# 2S1P_BatteryPack_V100.net
KiCad netlist of a schematic drawn in Altium Designer
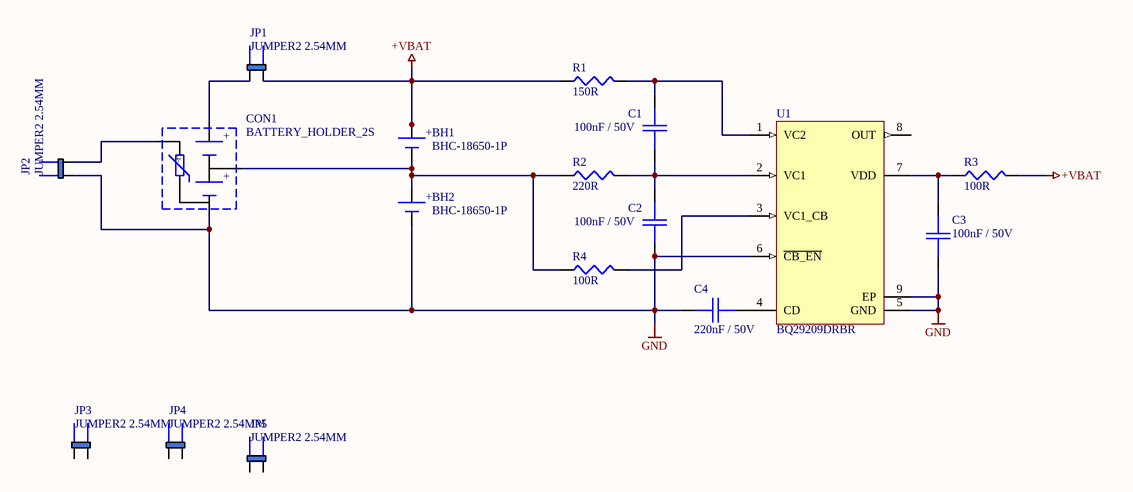
[diagram p0: 2S1P_BatteryPack_V100.SchDoc]

(export (version "E")
  (design (tool "Eeschema 10.0.6"))
  (components
    (comp (ref "BH1")
      (value "BHC-18650-1P")
      (footprint "18650_HOLDER")
      (description "18650 Battery Cell Holder THT")
      (libsource (lib "ALTIUM_DB_LIB") (part "BATTERY_HOLDER_18650"))
    )
    (comp (ref "BH2")
      (value "BHC-18650-1P")
      (footprint "18650_HOLDER")
      (description "18650 Battery Cell Holder THT")
      (libsource (lib "ALTIUM_DB_LIB") (part "BATTERY_HOLDER_18650"))
    )
    (comp (ref "C1")
      (value "100nF / 50V")
      (footprint "0805_C")
      (description "100nF 50V X7R")
      (fields (field (name "PART NUMBER") "SMD0805-100nF-50V"))
      (libsource (lib "ALTIUM_DB_LIB") (part "CAP_NONPOL"))
    )
    (comp (ref "C2")
      (value "100nF / 50V")
      (footprint "0805_C")
      (description "100nF 50V X7R")
      (fields (field (name "PART NUMBER") "SMD0805-100nF-50V"))
      (libsource (lib "ALTIUM_DB_LIB") (part "CAP_NONPOL"))
    )
    (comp (ref "C3")
      (value "100nF / 50V")
      (footprint "0805_C")
      (description "100nF 50V X7R")
      (fields (field (name "PART NUMBER") "SMD0805-100nF-50V"))
      (libsource (lib "ALTIUM_DB_LIB") (part "CAP_NONPOL"))
    )
    (comp (ref "C4")
      (value "220nF / 50V")
      (footprint "0805_C")
      (description "220nF 50V Y5V")
      (fields (field (name "PART NUMBER") "SMD0805-220nF-50V"))
      (libsource (lib "ALTIUM_DB_LIB") (part "CAP_NONPOL"))
    )
    (comp (ref "CON1")
      (value "BATTERY_HOLDER_2S")
      (footprint "MOLEX-53253-0470")
      (description "2S Battery with NTC thermistor")
      (libsource (lib "ALTIUM_DB_LIB") (part "BATTERY_HOLDER_2S"))
    )
    (comp (ref "JP1")
      (value "JUMPER2 2.54MM")
      (footprint "JUMPER_5")
      (libsource (lib "ALTIUM_DB_LIB") (part "JUMPER2"))
    )
    (comp (ref "JP2") (value "JUMPER2 2.54MM") (footprint "JUMPER_5") (libsource (lib "") (part "JUMPER2_1")))
    (comp (ref "JP3")
      (value "JUMPER2 2.54MM")
      (footprint "JUMPER_5")
      (libsource (lib "ALTIUM_DB_LIB") (part "JUMPER2"))
    )
    (comp (ref "JP4")
      (value "JUMPER2 2.54MM")
      (footprint "JUMPER_5")
      (libsource (lib "ALTIUM_DB_LIB") (part "JUMPER2"))
    )
    (comp (ref "JP5")
      (value "JUMPER2 2.54MM")
      (footprint "JUMPER_5")
      (libsource (lib "ALTIUM_DB_LIB") (part "JUMPER2"))
    )
    (comp (ref "R1")
      (value "150R")
      (footprint "0805")
      (description "150R 0805 0.125W 5%")
      (fields (field (name "PART NUMBER") "SMD0805-150R 5%"))
      (libsource (lib "ALTIUM_DB_LIB") (part "RESISTOR"))
    )
    (comp (ref "R2")
      (value "220R")
      (footprint "0805")
      (description "220R 0805 0.125W 5%")
      (fields (field (name "PART NUMBER") "SMD0805-220R 5%"))
      (libsource (lib "ALTIUM_DB_LIB") (part "RESISTOR"))
    )
    (comp (ref "R3")
      (value "100R")
      (footprint "0805")
      (description "100R 0805 0.125W 5%")
      (fields (field (name "PART NUMBER") "SMD0805-100R 5%"))
      (libsource (lib "ALTIUM_DB_LIB") (part "RESISTOR"))
    )
    (comp (ref "R4")
      (value "100R")
      (footprint "0805")
      (description "100R 0805 0.125W 5%")
      (fields (field (name "PART NUMBER") "SMD0805-100R 5%"))
      (libsource (lib "ALTIUM_DB_LIB") (part "RESISTOR"))
    )
    (comp (ref "U1")
      (value "BQ29209DRBR")
      (footprint "VSON-8")
      (fields (field (name "MANUFACTURER") "Texas Instruments"))
      (libsource (lib "ALTIUM_DB_LIB") (part "BQ29209DRBR"))
    )
  )
  (nets
    (net (code "1") (name "+VBAT") (class "Default")
      (node (ref "BH1") (pin "1") (pinfunction "1_1") (pintype "passive"))
      (node (ref "JP1") (pin "2") (pinfunction "2_2") (pintype "passive"))
      (node (ref "R1") (pin "1") (pintype "passive"))
      (node (ref "R3") (pin "1") (pintype "passive"))
    )
    (net (code "2") (name "GND") (class "Default")
      (node (ref "BH2") (pin "2") (pinfunction "2_2") (pintype "passive"))
      (node (ref "C2") (pin "2") (pintype "passive"))
      (node (ref "C3") (pin "1") (pintype "passive"))
      (node (ref "C4") (pin "1") (pintype "passive"))
      (node (ref "CON1") (pin "3") (pinfunction "3_3") (pintype "passive"))
      (node (ref "JP2") (pin "1") (pinfunction "1_1") (pintype "passive"))
      (node (ref "U1") (pin "5") (pinfunction "GND_5") (pintype "power_in"))
      (node (ref "U1") (pin "6") (pinfunction "~{CB_EN}_6") (pintype "input"))
      (node (ref "U1") (pin "9") (pinfunction "EP_9") (pintype "passive"))
    )
    (net (code "3") (name "Net-(BH1-Pad2)") (class "Default")
      (node (ref "BH1") (pin "2") (pinfunction "2_2") (pintype "passive"))
      (node (ref "BH2") (pin "1") (pinfunction "1_1") (pintype "passive"))
      (node (ref "CON1") (pin "2") (pinfunction "2_2") (pintype "passive"))
      (node (ref "R2") (pin "1") (pintype "passive"))
      (node (ref "R4") (pin "1") (pintype "passive"))
    )
    (net (code "4") (name "Net-(CON1-Pad1)") (class "Default")
      (node (ref "CON1") (pin "1") (pinfunction "1_1") (pintype "passive"))
      (node (ref "JP1") (pin "1") (pinfunction "1_1") (pintype "passive"))
    )
    (net (code "5") (name "Net-(CON1-Pad4)") (class "Default")
      (node (ref "CON1") (pin "4") (pintype "passive"))
      (node (ref "JP2") (pin "2") (pinfunction "2_2") (pintype "passive"))
    )
    (net (code "6") (name "Net-(U1-CD)") (class "Default")
      (node (ref "C4") (pin "2") (pintype "passive"))
      (node (ref "U1") (pin "4") (pinfunction "CD_4") (pintype "passive"))
    )
    (net (code "7") (name "Net-(U1-VC1)") (class "Default")
      (node (ref "C1") (pin "2") (pintype "passive"))
      (node (ref "C2") (pin "1") (pintype "passive"))
      (node (ref "R2") (pin "2") (pintype "passive"))
      (node (ref "U1") (pin "2") (pinfunction "VC1_2") (pintype "input"))
    )
    (net (code "8") (name "Net-(U1-VC1_CB)") (class "Default")
      (node (ref "R4") (pin "2") (pintype "passive"))
      (node (ref "U1") (pin "3") (pinfunction "VC1_CB_3") (pintype "input"))
    )
    (net (code "9") (name "Net-(U1-VC2)") (class "Default")
      (node (ref "C1") (pin "1") (pintype "passive"))
      (node (ref "R1") (pin "2") (pintype "passive"))
      (node (ref "U1") (pin "1") (pinfunction "VC2_1") (pintype "input"))
    )
    (net (code "10") (name "Net-(U1-VDD)") (class "Default")
      (node (ref "C3") (pin "2") (pintype "passive"))
      (node (ref "R3") (pin "2") (pintype "passive"))
      (node (ref "U1") (pin "7") (pinfunction "VDD_7") (pintype "power_in"))
    )
    (net (code "11") (name "unconnected-(JP3-Pad1)") (class "Default")
      (node (ref "JP3") (pin "1") (pinfunction "1_1") (pintype "passive"))
    )
    (net (code "12") (name "unconnected-(JP3-Pad2)") (class "Default")
      (node (ref "JP3") (pin "2") (pinfunction "2_2") (pintype "passive"))
    )
    (net (code "13") (name "unconnected-(JP4-Pad1)") (class "Default")
      (node (ref "JP4") (pin "1") (pinfunction "1_1") (pintype "passive"))
    )
    (net (code "14") (name "unconnected-(JP4-Pad2)") (class "Default")
      (node (ref "JP4") (pin "2") (pinfunction "2_2") (pintype "passive"))
    )
    (net (code "15") (name "unconnected-(JP5-Pad1)") (class "Default")
      (node (ref "JP5") (pin "1") (pinfunction "1_1") (pintype "passive"))
    )
    (net (code "16") (name "unconnected-(JP5-Pad2)") (class "Default")
      (node (ref "JP5") (pin "2") (pinfunction "2_2") (pintype "passive"))
    )
    (net (code "17") (name "unconnected-(U1-OUT-Pad8)") (class "Default")
      (node (ref "U1") (pin "8") (pinfunction "OUT_8") (pintype "output"))
    )
  )
)
